# 1ChAmp_circuit_TH.net
KiCad netlist of a schematic drawn in EAGLE
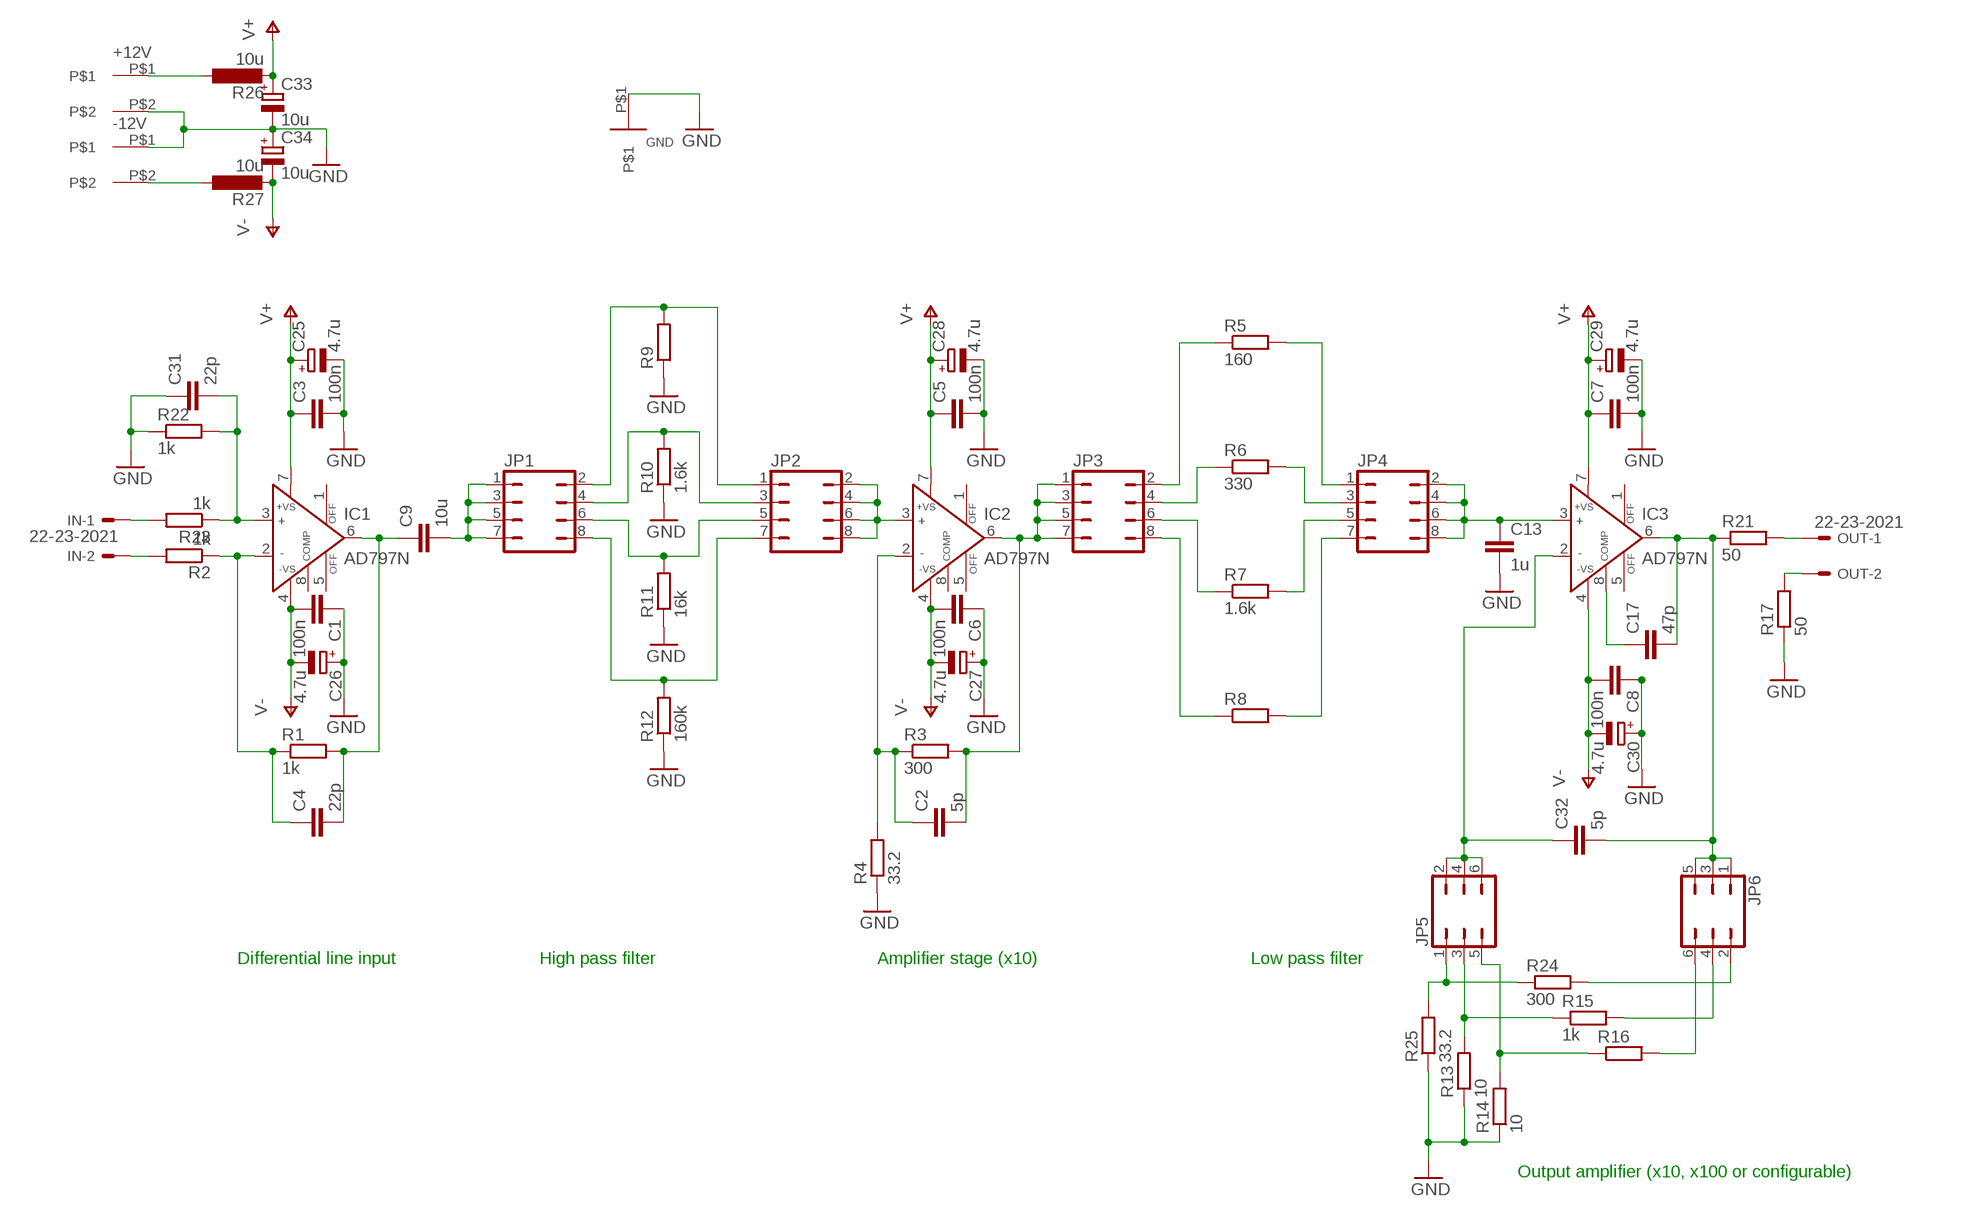
[diagram p0: schematic, sheet 1]

(export (version "E")
  (design (tool "Eeschema 10.0.6"))
  (components
    (comp (ref "+12V")
      (value "B2P-VH")
      (footprint "eagle-import:B2P-VH")
      (libsource (lib "eagle-import") (part "B2P-VH"))
    )
    (comp (ref "-12V")
      (value "B2P-VH")
      (footprint "eagle-import:B2P-VH")
      (libsource (lib "eagle-import") (part "B2P-VH"))
    )
    (comp (ref "C1")
      (value "100n")
      (footprint "eagle-import:C025-025X050")
      (libsource (lib "eagle-import") (part "C-EU025-025X050"))
    )
    (comp (ref "C2")
      (value "5p")
      (footprint "eagle-import:C025-025X050")
      (libsource (lib "eagle-import") (part "C-EU025-025X050"))
    )
    (comp (ref "C3")
      (value "100n")
      (footprint "eagle-import:C025-025X050")
      (libsource (lib "eagle-import") (part "C-EU025-025X050"))
    )
    (comp (ref "C4")
      (value "22p")
      (footprint "eagle-import:C025-025X050")
      (libsource (lib "eagle-import") (part "C-EU025-025X050"))
    )
    (comp (ref "C5")
      (value "100n")
      (footprint "eagle-import:C025-025X050")
      (libsource (lib "eagle-import") (part "C-EU025-025X050"))
    )
    (comp (ref "C6")
      (value "100n")
      (footprint "eagle-import:C025-025X050")
      (libsource (lib "eagle-import") (part "C-EU025-025X050"))
    )
    (comp (ref "C7")
      (value "100n")
      (footprint "eagle-import:C025-025X050")
      (libsource (lib "eagle-import") (part "C-EU025-025X050"))
    )
    (comp (ref "C8")
      (value "100n")
      (footprint "eagle-import:C025-025X050")
      (libsource (lib "eagle-import") (part "C-EU025-025X050"))
    )
    (comp (ref "C9")
      (value "10u")
      (footprint "eagle-import:C150-091X182")
      (libsource (lib "eagle-import") (part "C-EU150-091X182"))
    )
    (comp (ref "C13")
      (value "1u")
      (footprint "eagle-import:C025-025X050")
      (libsource (lib "eagle-import") (part "C-EU025-025X050"))
    )
    (comp (ref "C17")
      (value "47p")
      (footprint "eagle-import:C025-025X050")
      (libsource (lib "eagle-import") (part "C-EU025-025X050"))
    )
    (comp (ref "C25")
      (value "4.7u")
      (footprint "eagle-import:B45181A")
      (libsource (lib "eagle-import") (part "CPOL-EUB45181A"))
    )
    (comp (ref "C26")
      (value "4.7u")
      (footprint "eagle-import:B45181A")
      (libsource (lib "eagle-import") (part "CPOL-EUB45181A"))
    )
    (comp (ref "C27")
      (value "4.7u")
      (footprint "eagle-import:B45181A")
      (libsource (lib "eagle-import") (part "CPOL-EUB45181A"))
    )
    (comp (ref "C28")
      (value "4.7u")
      (footprint "eagle-import:B45181A")
      (libsource (lib "eagle-import") (part "CPOL-EUB45181A"))
    )
    (comp (ref "C29")
      (value "4.7u")
      (footprint "eagle-import:B45181A")
      (libsource (lib "eagle-import") (part "CPOL-EUB45181A"))
    )
    (comp (ref "C30")
      (value "4.7u")
      (footprint "eagle-import:B45181A")
      (libsource (lib "eagle-import") (part "CPOL-EUB45181A"))
    )
    (comp (ref "C31")
      (value "22p")
      (footprint "eagle-import:C025-025X050")
      (libsource (lib "eagle-import") (part "C-EU025-025X050"))
    )
    (comp (ref "C32")
      (value "5p")
      (footprint "eagle-import:C050-025X075")
      (libsource (lib "eagle-import") (part "C-EU050-025X075"))
    )
    (comp (ref "C33")
      (value "10u")
      (footprint "eagle-import:B45181A")
      (libsource (lib "eagle-import") (part "CPOL-EUB45181A"))
    )
    (comp (ref "C34")
      (value "10u")
      (footprint "eagle-import:B45181A")
      (libsource (lib "eagle-import") (part "CPOL-EUB45181A"))
    )
    (comp (ref "GND")
      (value "GND_CONNECTOR")
      (footprint "eagle-import:GND_CONNECTOR")
      (libsource (lib "eagle-import") (part "GND_CONNECTOR"))
    )
    (comp (ref "IC1")
      (value "AD797N")
      (footprint "eagle-import:DIL08")
      (fields (field (name "MF") "ALTERA CORPORATION") (field (name "MPN") "AD797ANZ"))
      (libsource (lib "eagle-import") (part "AD797N"))
    )
    (comp (ref "IC2")
      (value "AD797N")
      (footprint "eagle-import:DIL08")
      (fields (field (name "MF") "ALTERA CORPORATION") (field (name "MPN") "AD797ANZ"))
      (libsource (lib "eagle-import") (part "AD797N"))
    )
    (comp (ref "IC3")
      (value "AD797N")
      (footprint "eagle-import:DIL08")
      (fields (field (name "MF") "ALTERA CORPORATION") (field (name "MPN") "AD797ANZ"))
      (libsource (lib "eagle-import") (part "AD797N"))
    )
    (comp (ref "IN")
      (value "22-23-2021")
      (footprint "eagle-import:22-23-2021")
      (fields (field (name "MF") "MOLEX"))
      (libsource (lib "eagle-import") (part "22-23-2021"))
    )
    (comp (ref "JP1")
      (value "JP4Q")
      (footprint "eagle-import:JP4Q")
      (libsource (lib "eagle-import") (part "JP4Q"))
    )
    (comp (ref "JP2")
      (value "JP4Q")
      (footprint "eagle-import:JP4Q")
      (libsource (lib "eagle-import") (part "JP4Q"))
    )
    (comp (ref "JP3")
      (value "JP4Q")
      (footprint "eagle-import:JP4Q")
      (libsource (lib "eagle-import") (part "JP4Q"))
    )
    (comp (ref "JP4")
      (value "JP4Q")
      (footprint "eagle-import:JP4Q")
      (libsource (lib "eagle-import") (part "JP4Q"))
    )
    (comp (ref "JP5")
      (value "JP3Q")
      (footprint "eagle-import:JP3Q")
      (libsource (lib "eagle-import") (part "JP3Q"))
    )
    (comp (ref "JP6")
      (value "JP3Q")
      (footprint "eagle-import:JP3Q")
      (libsource (lib "eagle-import") (part "JP3Q"))
    )
    (comp (ref "OUT")
      (value "22-23-2021")
      (footprint "eagle-import:22-23-2021")
      (fields (field (name "MF") "MOLEX"))
      (libsource (lib "eagle-import") (part "22-23-2021"))
    )
    (comp (ref "R1")
      (value "1k")
      (footprint "eagle-import:0204_5")
      (libsource (lib "eagle-import") (part "R-EU_0204/5"))
    )
    (comp (ref "R2")
      (value "1k")
      (footprint "eagle-import:0204_5")
      (libsource (lib "eagle-import") (part "R-EU_0204/5"))
    )
    (comp (ref "R3")
      (value "300")
      (footprint "eagle-import:0204_5")
      (libsource (lib "eagle-import") (part "R-EU_0204/5"))
    )
    (comp (ref "R4")
      (value "33.2")
      (footprint "eagle-import:0204_5")
      (libsource (lib "eagle-import") (part "R-EU_0204/5"))
    )
    (comp (ref "R5")
      (value "160")
      (footprint "eagle-import:0204_5")
      (libsource (lib "eagle-import") (part "R-EU_0204/5"))
    )
    (comp (ref "R6")
      (value "330")
      (footprint "eagle-import:0204_5")
      (libsource (lib "eagle-import") (part "R-EU_0204/5"))
    )
    (comp (ref "R7")
      (value "1.6k")
      (footprint "eagle-import:0204_5")
      (libsource (lib "eagle-import") (part "R-EU_0204/5"))
    )
    (comp (ref "R8")
      (value "R-EU_0204/5")
      (footprint "eagle-import:0204_5")
      (libsource (lib "eagle-import") (part "resistor_R-EU_0204/5"))
    )
    (comp (ref "R9")
      (value "R-EU_0204/5")
      (footprint "eagle-import:0204_5")
      (libsource (lib "eagle-import") (part "R-EU_0204/5"))
    )
    (comp (ref "R10")
      (value "1.6k")
      (footprint "eagle-import:0204_5")
      (libsource (lib "eagle-import") (part "R-EU_0204/5"))
    )
    (comp (ref "R11")
      (value "16k")
      (footprint "eagle-import:0204_5")
      (libsource (lib "eagle-import") (part "R-EU_0204/5"))
    )
    (comp (ref "R12")
      (value "160k")
      (footprint "eagle-import:0204_5")
      (libsource (lib "eagle-import") (part "R-EU_0204/5"))
    )
    (comp (ref "R13")
      (value "10")
      (footprint "eagle-import:0204_5")
      (libsource (lib "eagle-import") (part "R-EU_0204/5"))
    )
    (comp (ref "R14")
      (value "10")
      (footprint "eagle-import:0204_5")
      (libsource (lib "eagle-import") (part "R-EU_0204/5"))
    )
    (comp (ref "R15")
      (value "1k")
      (footprint "eagle-import:0204_5")
      (libsource (lib "eagle-import") (part "R-EU_0204/5"))
    )
    (comp (ref "R16")
      (value "R-EU_0204/5")
      (footprint "eagle-import:0204_5")
      (libsource (lib "eagle-import") (part "R-EU_0204/5"))
    )
    (comp (ref "R17")
      (value "50")
      (footprint "eagle-import:0204_5")
      (libsource (lib "eagle-import") (part "R-EU_0204/5"))
    )
    (comp (ref "R21")
      (value "50")
      (footprint "eagle-import:0204_5")
      (libsource (lib "eagle-import") (part "R-EU_0204/5"))
    )
    (comp (ref "R22")
      (value "1k")
      (footprint "eagle-import:0204_5")
      (libsource (lib "eagle-import") (part "R-EU_0204/5"))
    )
    (comp (ref "R23")
      (value "1k")
      (footprint "eagle-import:0204_5")
      (libsource (lib "eagle-import") (part "R-EU_0204/5"))
    )
    (comp (ref "R24")
      (value "300")
      (footprint "eagle-import:0204_5")
      (libsource (lib "eagle-import") (part "R-EU_0204/5"))
    )
    (comp (ref "R25")
      (value "33.2")
      (footprint "eagle-import:0204_5")
      (libsource (lib "eagle-import") (part "R-EU_0204/5"))
    )
    (comp (ref "R26")
      (value "10u")
      (footprint "eagle-import:RFS1113")
      (libsource (lib "eagle-import") (part "L-EU"))
    )
    (comp (ref "R27")
      (value "10u")
      (footprint "eagle-import:RFS1113")
      (libsource (lib "eagle-import") (part "L-EU"))
    )
  )
  (nets
    (net (code "1") (name "GND") (class "Default")
      (node (ref "+12V") (pin "P$2") (pinfunction "P$2_P$2") (pintype "bidirectional"))
      (node (ref "-12V") (pin "P$1") (pinfunction "P$1_P$1") (pintype "bidirectional"))
      (node (ref "C1") (pin "1") (pinfunction "1_1") (pintype "passive"))
      (node (ref "C13") (pin "2") (pinfunction "2_2") (pintype "passive"))
      (node (ref "C25") (pin "-") (pinfunction "-_-") (pintype "passive"))
      (node (ref "C26") (pin "+") (pinfunction "+_+") (pintype "passive"))
      (node (ref "C27") (pin "+") (pinfunction "+_+") (pintype "passive"))
      (node (ref "C28") (pin "-") (pinfunction "-_-") (pintype "passive"))
      (node (ref "C29") (pin "-") (pinfunction "-_-") (pintype "passive"))
      (node (ref "C3") (pin "2") (pinfunction "2_2") (pintype "passive"))
      (node (ref "C30") (pin "+") (pinfunction "+_+") (pintype "passive"))
      (node (ref "C31") (pin "1") (pinfunction "1_1") (pintype "passive"))
      (node (ref "C33") (pin "-") (pinfunction "-_-") (pintype "passive"))
      (node (ref "C34") (pin "+") (pinfunction "+_+") (pintype "passive"))
      (node (ref "C5") (pin "2") (pinfunction "2_2") (pintype "passive"))
      (node (ref "C6") (pin "1") (pinfunction "1_1") (pintype "passive"))
      (node (ref "C7") (pin "2") (pinfunction "2_2") (pintype "passive"))
      (node (ref "C8") (pin "1") (pinfunction "1_1") (pintype "passive"))
      (node (ref "GND") (pin "P$1") (pinfunction "P$1_P$1") (pintype "bidirectional"))
      (node (ref "R10") (pin "1") (pinfunction "1_1") (pintype "passive"))
      (node (ref "R11") (pin "1") (pinfunction "1_1") (pintype "passive"))
      (node (ref "R12") (pin "1") (pinfunction "1_1") (pintype "passive"))
      (node (ref "R13") (pin "1") (pinfunction "1_1") (pintype "passive"))
      (node (ref "R14") (pin "1") (pinfunction "1_1") (pintype "passive"))
      (node (ref "R17") (pin "1") (pinfunction "1_1") (pintype "passive"))
      (node (ref "R22") (pin "1") (pinfunction "1_1") (pintype "passive"))
      (node (ref "R25") (pin "1") (pinfunction "1_1") (pintype "passive"))
      (node (ref "R4") (pin "1") (pinfunction "1_1") (pintype "passive"))
      (node (ref "R9") (pin "1") (pinfunction "1_1") (pintype "passive"))
    )
    (net (code "2") (name "Net-(C9-Pad2)") (class "Default")
      (node (ref "C9") (pin "2") (pinfunction "2_2") (pintype "passive"))
      (node (ref "JP1") (pin "1") (pinfunction "1_1") (pintype "passive"))
      (node (ref "JP1") (pin "3") (pinfunction "3_3") (pintype "passive"))
      (node (ref "JP1") (pin "5") (pinfunction "5_5") (pintype "passive"))
      (node (ref "JP1") (pin "7") (pinfunction "7_7") (pintype "passive"))
    )
    (net (code "3") (name "Net-(IC1-IN+)") (class "Default")
      (node (ref "C31") (pin "2") (pinfunction "2_2") (pintype "passive"))
      (node (ref "IC1") (pin "3") (pinfunction "IN+_3") (pintype "input"))
      (node (ref "R22") (pin "2") (pinfunction "2_2") (pintype "passive"))
      (node (ref "R23") (pin "1") (pinfunction "1_1") (pintype "passive"))
    )
    (net (code "4") (name "Net-(IC1-IN-)") (class "Default")
      (node (ref "C4") (pin "1") (pinfunction "1_1") (pintype "passive"))
      (node (ref "IC1") (pin "2") (pinfunction "IN-_2") (pintype "input"))
      (node (ref "R1") (pin "1") (pinfunction "1_1") (pintype "passive"))
      (node (ref "R2") (pin "1") (pinfunction "1_1") (pintype "passive"))
    )
    (net (code "5") (name "Net-(IC1-OUT)") (class "Default")
      (node (ref "C4") (pin "2") (pinfunction "2_2") (pintype "passive"))
      (node (ref "C9") (pin "1") (pinfunction "1_1") (pintype "passive"))
      (node (ref "IC1") (pin "6") (pinfunction "OUT_6") (pintype "output"))
      (node (ref "R1") (pin "2") (pinfunction "2_2") (pintype "passive"))
    )
    (net (code "6") (name "Net-(IC2-IN+)") (class "Default")
      (node (ref "IC2") (pin "3") (pinfunction "IN+_3") (pintype "input"))
      (node (ref "JP2") (pin "2") (pinfunction "2_2") (pintype "passive"))
      (node (ref "JP2") (pin "4") (pinfunction "4_4") (pintype "passive"))
      (node (ref "JP2") (pin "6") (pinfunction "6_6") (pintype "passive"))
      (node (ref "JP2") (pin "8") (pinfunction "8_8") (pintype "passive"))
    )
    (net (code "7") (name "Net-(IC2-IN-)") (class "Default")
      (node (ref "C2") (pin "1") (pinfunction "1_1") (pintype "passive"))
      (node (ref "IC2") (pin "2") (pinfunction "IN-_2") (pintype "input"))
      (node (ref "R3") (pin "1") (pinfunction "1_1") (pintype "passive"))
      (node (ref "R4") (pin "2") (pinfunction "2_2") (pintype "passive"))
    )
    (net (code "8") (name "Net-(IC2-OUT)") (class "Default")
      (node (ref "C2") (pin "2") (pinfunction "2_2") (pintype "passive"))
      (node (ref "IC2") (pin "6") (pinfunction "OUT_6") (pintype "output"))
      (node (ref "JP3") (pin "1") (pinfunction "1_1") (pintype "passive"))
      (node (ref "JP3") (pin "3") (pinfunction "3_3") (pintype "passive"))
      (node (ref "JP3") (pin "5") (pinfunction "5_5") (pintype "passive"))
      (node (ref "JP3") (pin "7") (pinfunction "7_7") (pintype "passive"))
      (node (ref "R3") (pin "2") (pinfunction "2_2") (pintype "passive"))
    )
    (net (code "9") (name "Net-(IC3-COMP)") (class "Default")
      (node (ref "C17") (pin "1") (pinfunction "1_1") (pintype "passive"))
      (node (ref "IC3") (pin "8") (pinfunction "COMP_8") (pintype "passive"))
    )
    (net (code "10") (name "Net-(IC3-IN+)") (class "Default")
      (node (ref "C13") (pin "1") (pinfunction "1_1") (pintype "passive"))
      (node (ref "IC3") (pin "3") (pinfunction "IN+_3") (pintype "input"))
      (node (ref "JP4") (pin "2") (pinfunction "2_2") (pintype "passive"))
      (node (ref "JP4") (pin "4") (pinfunction "4_4") (pintype "passive"))
      (node (ref "JP4") (pin "6") (pinfunction "6_6") (pintype "passive"))
      (node (ref "JP4") (pin "8") (pinfunction "8_8") (pintype "passive"))
    )
    (net (code "11") (name "Net-(IC3-IN-)") (class "Default")
      (node (ref "C32") (pin "1") (pinfunction "1_1") (pintype "passive"))
      (node (ref "IC3") (pin "2") (pinfunction "IN-_2") (pintype "input"))
      (node (ref "JP5") (pin "2") (pinfunction "2_2") (pintype "passive"))
      (node (ref "JP5") (pin "4") (pinfunction "4_4") (pintype "passive"))
      (node (ref "JP5") (pin "6") (pinfunction "6_6") (pintype "passive"))
    )
    (net (code "12") (name "Net-(IC3-OUT)") (class "Default")
      (node (ref "C17") (pin "2") (pinfunction "2_2") (pintype "passive"))
      (node (ref "C32") (pin "2") (pinfunction "2_2") (pintype "passive"))
      (node (ref "IC3") (pin "6") (pinfunction "OUT_6") (pintype "output"))
      (node (ref "JP6") (pin "1") (pinfunction "1_1") (pintype "passive"))
      (node (ref "JP6") (pin "3") (pinfunction "3_3") (pintype "passive"))
      (node (ref "JP6") (pin "5") (pinfunction "5_5") (pintype "passive"))
      (node (ref "R21") (pin "1") (pinfunction "1_1") (pintype "passive"))
    )
    (net (code "13") (name "Net-(INA-S)") (class "Default")
      (node (ref "IN") (pin "1") (pinfunction "S_1") (pintype "passive"))
      (node (ref "R23") (pin "2") (pinfunction "2_2") (pintype "passive"))
    )
    (net (code "14") (name "Net-(INB-S)") (class "Default")
      (node (ref "IN") (pin "2") (pinfunction "S_2") (pintype "passive"))
      (node (ref "R2") (pin "2") (pinfunction "2_2") (pintype "passive"))
    )
    (net (code "15") (name "Net-(JP1-Pad2)") (class "Default")
      (node (ref "JP1") (pin "2") (pinfunction "2_2") (pintype "passive"))
      (node (ref "JP2") (pin "1") (pinfunction "1_1") (pintype "passive"))
      (node (ref "R9") (pin "2") (pinfunction "2_2") (pintype "passive"))
    )
    (net (code "16") (name "Net-(JP1-Pad4)") (class "Default")
      (node (ref "JP1") (pin "4") (pinfunction "4_4") (pintype "passive"))
      (node (ref "JP2") (pin "3") (pinfunction "3_3") (pintype "passive"))
      (node (ref "R10") (pin "2") (pinfunction "2_2") (pintype "passive"))
    )
    (net (code "17") (name "Net-(JP1-Pad6)") (class "Default")
      (node (ref "JP1") (pin "6") (pinfunction "6_6") (pintype "passive"))
      (node (ref "JP2") (pin "5") (pinfunction "5_5") (pintype "passive"))
      (node (ref "R11") (pin "2") (pinfunction "2_2") (pintype "passive"))
    )
    (net (code "18") (name "Net-(JP1-Pad8)") (class "Default")
      (node (ref "JP1") (pin "8") (pinfunction "8_8") (pintype "passive"))
      (node (ref "JP2") (pin "7") (pinfunction "7_7") (pintype "passive"))
      (node (ref "R12") (pin "2") (pinfunction "2_2") (pintype "passive"))
    )
    (net (code "19") (name "Net-(JP3-Pad2)") (class "Default")
      (node (ref "JP3") (pin "2") (pinfunction "2_2") (pintype "passive"))
      (node (ref "R5") (pin "1") (pinfunction "1_1") (pintype "passive"))
    )
    (net (code "20") (name "Net-(JP3-Pad4)") (class "Default")
      (node (ref "JP3") (pin "4") (pinfunction "4_4") (pintype "passive"))
      (node (ref "R6") (pin "1") (pinfunction "1_1") (pintype "passive"))
    )
    (net (code "21") (name "Net-(JP3-Pad6)") (class "Default")
      (node (ref "JP3") (pin "6") (pinfunction "6_6") (pintype "passive"))
      (node (ref "R7") (pin "1") (pinfunction "1_1") (pintype "passive"))
    )
    (net (code "22") (name "Net-(JP3-Pad8)") (class "Default")
      (node (ref "JP3") (pin "8") (pinfunction "8_8") (pintype "passive"))
      (node (ref "R8") (pin "1") (pinfunction "1_1") (pintype "passive"))
    )
    (net (code "23") (name "Net-(JP4-Pad1)") (class "Default")
      (node (ref "JP4") (pin "1") (pinfunction "1_1") (pintype "passive"))
      (node (ref "R5") (pin "2") (pinfunction "2_2") (pintype "passive"))
    )
    (net (code "24") (name "Net-(JP4-Pad3)") (class "Default")
      (node (ref "JP4") (pin "3") (pinfunction "3_3") (pintype "passive"))
      (node (ref "R6") (pin "2") (pinfunction "2_2") (pintype "passive"))
    )
    (net (code "25") (name "Net-(JP4-Pad5)") (class "Default")
      (node (ref "JP4") (pin "5") (pinfunction "5_5") (pintype "passive"))
      (node (ref "R7") (pin "2") (pinfunction "2_2") (pintype "passive"))
    )
    (net (code "26") (name "Net-(JP4-Pad7)") (class "Default")
      (node (ref "JP4") (pin "7") (pinfunction "7_7") (pintype "passive"))
      (node (ref "R8") (pin "2") (pinfunction "2_2") (pintype "passive"))
    )
    (net (code "27") (name "Net-(JP5-Pad1)") (class "Default")
      (node (ref "JP5") (pin "1") (pinfunction "1_1") (pintype "passive"))
      (node (ref "R24") (pin "1") (pinfunction "1_1") (pintype "passive"))
      (node (ref "R25") (pin "2") (pinfunction "2_2") (pintype "passive"))
    )
    (net (code "28") (name "Net-(JP5-Pad3)") (class "Default")
      (node (ref "JP5") (pin "3") (pinfunction "3_3") (pintype "passive"))
      (node (ref "R13") (pin "2") (pinfunction "2_2") (pintype "passive"))
      (node (ref "R15") (pin "1") (pinfunction "1_1") (pintype "passive"))
    )
    (net (code "29") (name "Net-(JP5-Pad5)") (class "Default")
      (node (ref "JP5") (pin "5") (pinfunction "5_5") (pintype "passive"))
      (node (ref "R14") (pin "2") (pinfunction "2_2") (pintype "passive"))
      (node (ref "R16") (pin "1") (pinfunction "1_1") (pintype "passive"))
    )
    (net (code "30") (name "Net-(JP6-Pad2)") (class "Default")
      (node (ref "JP6") (pin "2") (pinfunction "2_2") (pintype "passive"))
      (node (ref "R24") (pin "2") (pinfunction "2_2") (pintype "passive"))
    )
    (net (code "31") (name "Net-(JP6-Pad4)") (class "Default")
      (node (ref "JP6") (pin "4") (pinfunction "4_4") (pintype "passive"))
      (node (ref "R15") (pin "2") (pinfunction "2_2") (pintype "passive"))
    )
    (net (code "32") (name "Net-(JP6-Pad6)") (class "Default")
      (node (ref "JP6") (pin "6") (pinfunction "6_6") (pintype "passive"))
      (node (ref "R16") (pin "2") (pinfunction "2_2") (pintype "passive"))
    )
    (net (code "33") (name "Net-(OUTA-S)") (class "Default")
      (node (ref "OUT") (pin "1") (pinfunction "S_1") (pintype "passive"))
      (node (ref "R21") (pin "2") (pinfunction "2_2") (pintype "passive"))
    )
    (net (code "34") (name "Net-(OUTB-S)") (class "Default")
      (node (ref "OUT") (pin "2") (pinfunction "S_2") (pintype "passive"))
      (node (ref "R17") (pin "2") (pinfunction "2_2") (pintype "passive"))
    )
    (net (code "35") (name "Net-(R26-1)") (class "Default")
      (node (ref "+12V") (pin "P$1") (pinfunction "P$1_P$1") (pintype "bidirectional"))
      (node (ref "R26") (pin "P$1") (pinfunction "1_P$1") (pintype "passive"))
    )
    (net (code "36") (name "Net-(R27-1)") (class "Default")
      (node (ref "-12V") (pin "P$2") (pinfunction "P$2_P$2") (pintype "bidirectional"))
      (node (ref "R27") (pin "P$1") (pinfunction "1_P$1") (pintype "passive"))
    )
    (net (code "37") (name "V+") (class "Default")
      (node (ref "C25") (pin "+") (pinfunction "+_+") (pintype "passive"))
      (node (ref "C28") (pin "+") (pinfunction "+_+") (pintype "passive"))
      (node (ref "C29") (pin "+") (pinfunction "+_+") (pintype "passive"))
      (node (ref "C3") (pin "1") (pinfunction "1_1") (pintype "passive"))
      (node (ref "C33") (pin "+") (pinfunction "+_+") (pintype "passive"))
      (node (ref "C5") (pin "1") (pinfunction "1_1") (pintype "passive"))
      (node (ref "C7") (pin "1") (pinfunction "1_1") (pintype "passive"))
      (node (ref "IC1") (pin "7") (pinfunction "+VS_7") (pintype "input"))
      (node (ref "IC2") (pin "7") (pinfunction "+VS_7") (pintype "input"))
      (node (ref "IC3") (pin "7") (pinfunction "+VS_7") (pintype "input"))
      (node (ref "R26") (pin "P$2") (pinfunction "2_P$2") (pintype "passive"))
    )
    (net (code "38") (name "V-") (class "Default")
      (node (ref "C1") (pin "2") (pinfunction "2_2") (pintype "passive"))
      (node (ref "C26") (pin "-") (pinfunction "-_-") (pintype "passive"))
      (node (ref "C27") (pin "-") (pinfunction "-_-") (pintype "passive"))
      (node (ref "C30") (pin "-") (pinfunction "-_-") (pintype "passive"))
      (node (ref "C34") (pin "-") (pinfunction "-_-") (pintype "passive"))
      (node (ref "C6") (pin "2") (pinfunction "2_2") (pintype "passive"))
      (node (ref "C8") (pin "2") (pinfunction "2_2") (pintype "passive"))
      (node (ref "IC1") (pin "4") (pinfunction "-VS_4") (pintype "input"))
      (node (ref "IC2") (pin "4") (pinfunction "-VS_4") (pintype "input"))
      (node (ref "IC3") (pin "4") (pinfunction "-VS_4") (pintype "input"))
      (node (ref "R27") (pin "P$2") (pinfunction "2_P$2") (pintype "passive"))
    )
    (net (code "39") (name "unconnected-(IC1-COMP-Pad8)") (class "Default")
      (node (ref "IC1") (pin "8") (pinfunction "COMP_8") (pintype "passive"))
    )
    (net (code "40") (name "unconnected-(IC1-OFF-Pad1)") (class "Default")
      (node (ref "IC1") (pin "1") (pinfunction "OFF_1") (pintype "passive"))
    )
    (net (code "41") (name "unconnected-(IC1-OFF-Pad5)") (class "Default")
      (node (ref "IC1") (pin "5") (pinfunction "OFF_5") (pintype "passive"))
    )
    (net (code "42") (name "unconnected-(IC2-COMP-Pad8)") (class "Default")
      (node (ref "IC2") (pin "8") (pinfunction "COMP_8") (pintype "passive"))
    )
    (net (code "43") (name "unconnected-(IC2-OFF-Pad1)") (class "Default")
      (node (ref "IC2") (pin "1") (pinfunction "OFF_1") (pintype "passive"))
    )
    (net (code "44") (name "unconnected-(IC2-OFF-Pad5)") (class "Default")
      (node (ref "IC2") (pin "5") (pinfunction "OFF_5") (pintype "passive"))
    )
    (net (code "45") (name "unconnected-(IC3-OFF-Pad1)") (class "Default")
      (node (ref "IC3") (pin "1") (pinfunction "OFF_1") (pintype "passive"))
    )
    (net (code "46") (name "unconnected-(IC3-OFF-Pad5)") (class "Default")
      (node (ref "IC3") (pin "5") (pinfunction "OFF_5") (pintype "passive"))
    )
  )
)
